# PCM5102a.net
KiCad netlist of a schematic drawn in EAGLE
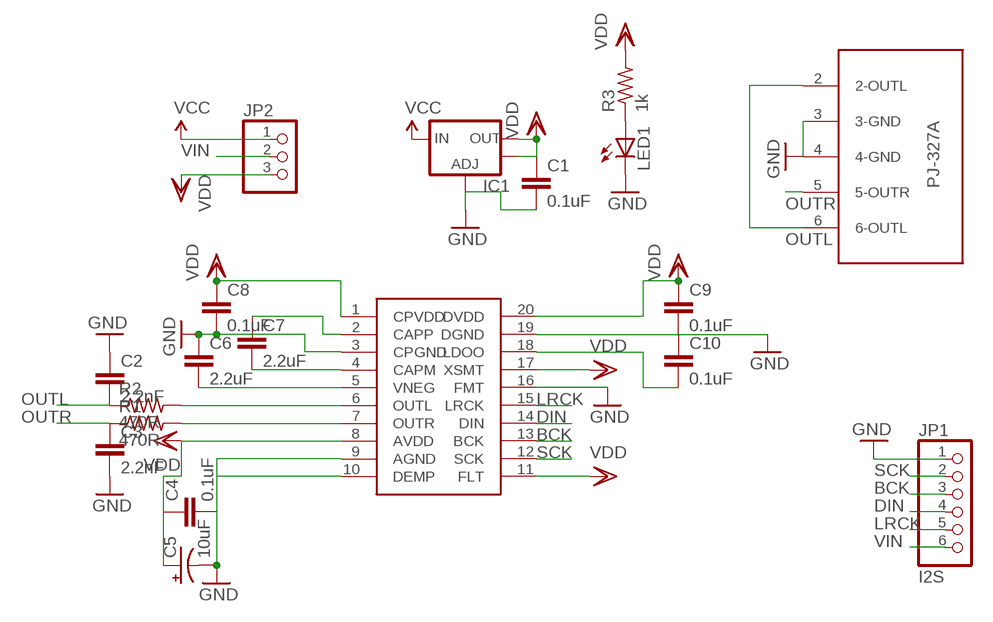
[diagram p0: schematic, sheet 1]

(export (version "E")
  (design (tool "Eeschema 10.0.6"))
  (components
    (comp (ref "C1")
      (value "0.1uF")
      (footprint "eagle-import:1206")
      (libsource (lib "eagle-import") (part "2.2UF-CERCAP-10009"))
    )
    (comp (ref "C2")
      (value "2.2nF")
      (footprint "eagle-import:C5B2.5")
      (libsource (lib "eagle-import") (part "C5/2.5"))
    )
    (comp (ref "C3")
      (value "2.2nF")
      (footprint "eagle-import:C5B2.5")
      (libsource (lib "eagle-import") (part "C5/2.5"))
    )
    (comp (ref "C4")
      (value "0.1uF")
      (footprint "eagle-import:1206")
      (libsource (lib "eagle-import") (part "2.2UF-CERCAP-10009"))
    )
    (comp (ref "C5")
      (value "10uF")
      (footprint "eagle-import:NIPPON_F80")
      (libsource (lib "eagle-import") (part "CAP_POLF80"))
    )
    (comp (ref "C6")
      (value "2.2uF")
      (footprint "eagle-import:1206")
      (libsource (lib "eagle-import") (part "2.2UF-CERCAP-10009"))
    )
    (comp (ref "C7")
      (value "2.2uF")
      (footprint "eagle-import:1206")
      (libsource (lib "eagle-import") (part "2.2UF-CERCAP-10009"))
    )
    (comp (ref "C8")
      (value "0.1uF")
      (footprint "eagle-import:1206")
      (libsource (lib "eagle-import") (part "2.2UF-CERCAP-10009"))
    )
    (comp (ref "C9")
      (value "0.1uF")
      (footprint "eagle-import:1206")
      (libsource (lib "eagle-import") (part "2.2UF-CERCAP-10009"))
    )
    (comp (ref "C10")
      (value "0.1uF")
      (footprint "eagle-import:1206")
      (libsource (lib "eagle-import") (part "2.2UF-CERCAP-10009"))
    )
    (comp (ref "IC1")
      (value "V_REG_LM1117SOT223")
      (footprint "eagle-import:SOT223")
      (libsource (lib "eagle-import") (part "V_REG_LM1117SOT223"))
    )
    (comp (ref "JP1")
      (value "I2S")
      (footprint "eagle-import:1X06_90")
      (libsource (lib "eagle-import") (part "PINHD-1X6/90"))
    )
    (comp (ref "JP2")
      (value "PINHD-1X3")
      (footprint "eagle-import:1X03")
      (libsource (lib "eagle-import") (part "PINHD-1X3"))
    )
    (comp (ref "LED1")
      (value "LEDCHIP-LED0805")
      (footprint "eagle-import:CHIP-LED0805")
      (libsource (lib "eagle-import") (part "LEDCHIP-LED0805"))
    )
    (comp (ref "R1")
      (value "470R")
      (footprint "eagle-import:0207_10")
      (libsource (lib "eagle-import") (part "R-US_0207/10"))
    )
    (comp (ref "R2")
      (value "470R")
      (footprint "eagle-import:0207_10")
      (libsource (lib "eagle-import") (part "R-US_0207/10"))
    )
    (comp (ref "R3")
      (value "1k")
      (footprint "eagle-import:0207_10")
      (libsource (lib "eagle-import") (part "R-US_0207/10"))
    )
    (comp (ref "U$1")
      (value "PCM5102")
      (footprint "eagle-import:TSSOP20")
      (libsource (lib "eagle-import") (part "PCM5102"))
    )
    (comp (ref "U$2")
      (value "PJ-327A")
      (footprint "eagle-import:PJ-327A")
      (libsource (lib "eagle-import") (part "PJ-327A"))
    )
  )
  (nets
    (net (code "1") (name "/BCK") (class "Default")
      (node (ref "JP1") (pin "3") (pinfunction "3_3") (pintype "passive"))
      (node (ref "U$1") (pin "13") (pinfunction "BCK_13") (pintype "bidirectional"))
    )
    (net (code "2") (name "/DIN") (class "Default")
      (node (ref "JP1") (pin "4") (pinfunction "4_4") (pintype "passive"))
      (node (ref "U$1") (pin "14") (pinfunction "DIN_14") (pintype "bidirectional"))
    )
    (net (code "3") (name "/LRCK") (class "Default")
      (node (ref "JP1") (pin "5") (pinfunction "5_5") (pintype "passive"))
      (node (ref "U$1") (pin "15") (pinfunction "LRCK_15") (pintype "bidirectional"))
    )
    (net (code "4") (name "/OUTL") (class "Default")
      (node (ref "C2") (pin "2") (pinfunction "2_2") (pintype "passive"))
      (node (ref "R2") (pin "1") (pinfunction "1_1") (pintype "passive"))
      (node (ref "U$2") (pin "2") (pinfunction "2-OUTL_2") (pintype "bidirectional"))
      (node (ref "U$2") (pin "6") (pinfunction "6-OUTL_6") (pintype "bidirectional"))
    )
    (net (code "5") (name "/OUTR") (class "Default")
      (node (ref "C3") (pin "1") (pinfunction "1_1") (pintype "passive"))
      (node (ref "R1") (pin "1") (pinfunction "1_1") (pintype "passive"))
      (node (ref "U$2") (pin "5") (pinfunction "5-OUTR_5") (pintype "bidirectional"))
    )
    (net (code "6") (name "/SCK") (class "Default")
      (node (ref "JP1") (pin "2") (pinfunction "2_2") (pintype "passive"))
      (node (ref "U$1") (pin "12") (pinfunction "SCK_12") (pintype "bidirectional"))
    )
    (net (code "7") (name "/VIN") (class "Default")
      (node (ref "JP1") (pin "6") (pinfunction "6_6") (pintype "passive"))
      (node (ref "JP2") (pin "2") (pinfunction "2_2") (pintype "passive"))
    )
    (net (code "8") (name "GND") (class "Default")
      (node (ref "C1") (pin "2") (pinfunction "2_2") (pintype "passive"))
      (node (ref "C10") (pin "1") (pinfunction "1_1") (pintype "passive"))
      (node (ref "C2") (pin "1") (pinfunction "1_1") (pintype "passive"))
      (node (ref "C3") (pin "2") (pinfunction "2_2") (pintype "passive"))
      (node (ref "C4") (pin "2") (pinfunction "2_2") (pintype "passive"))
      (node (ref "C5") (pin "-") (pinfunction "-_-") (pintype "passive"))
      (node (ref "C6") (pin "1") (pinfunction "1_1") (pintype "passive"))
      (node (ref "C8") (pin "2") (pinfunction "2_2") (pintype "passive"))
      (node (ref "C9") (pin "2") (pinfunction "2_2") (pintype "passive"))
      (node (ref "IC1") (pin "1") (pinfunction "ADJ_1") (pintype "input"))
      (node (ref "JP1") (pin "1") (pinfunction "1_1") (pintype "passive"))
      (node (ref "LED1") (pin "C") (pinfunction "C_C") (pintype "passive"))
      (node (ref "U$1") (pin "10") (pinfunction "DEMP_10") (pintype "bidirectional"))
      (node (ref "U$1") (pin "16") (pinfunction "FMT_16") (pintype "bidirectional"))
      (node (ref "U$1") (pin "19") (pinfunction "DGND_19") (pintype "bidirectional"))
      (node (ref "U$1") (pin "3") (pinfunction "CPGND_3") (pintype "bidirectional"))
      (node (ref "U$1") (pin "9") (pinfunction "AGND_9") (pintype "bidirectional"))
      (node (ref "U$2") (pin "3") (pinfunction "3-GND_3") (pintype "bidirectional"))
      (node (ref "U$2") (pin "4") (pinfunction "4-GND_4") (pintype "bidirectional"))
    )
    (net (code "9") (name "Net-(LED1-PadA)") (class "Default")
      (node (ref "LED1") (pin "A") (pinfunction "A_A") (pintype "passive"))
      (node (ref "R3") (pin "1") (pinfunction "1_1") (pintype "passive"))
    )
    (net (code "10") (name "Net-(U$1-CAPM)") (class "Default")
      (node (ref "C7") (pin "2") (pinfunction "2_2") (pintype "passive"))
      (node (ref "U$1") (pin "4") (pinfunction "CAPM_4") (pintype "bidirectional"))
    )
    (net (code "11") (name "Net-(U$1-CAPP)") (class "Default")
      (node (ref "C7") (pin "1") (pinfunction "1_1") (pintype "passive"))
      (node (ref "U$1") (pin "2") (pinfunction "CAPP_2") (pintype "bidirectional"))
    )
    (net (code "12") (name "Net-(U$1-LDOO)") (class "Default")
      (node (ref "C10") (pin "2") (pinfunction "2_2") (pintype "passive"))
      (node (ref "U$1") (pin "18") (pinfunction "LDOO_18") (pintype "bidirectional"))
    )
    (net (code "13") (name "Net-(U$1-OUTL)") (class "Default")
      (node (ref "R2") (pin "2") (pinfunction "2_2") (pintype "passive"))
      (node (ref "U$1") (pin "6") (pinfunction "OUTL_6") (pintype "bidirectional"))
    )
    (net (code "14") (name "Net-(U$1-OUTR)") (class "Default")
      (node (ref "R1") (pin "2") (pinfunction "2_2") (pintype "passive"))
      (node (ref "U$1") (pin "7") (pinfunction "OUTR_7") (pintype "bidirectional"))
    )
    (net (code "15") (name "Net-(U$1-VNEG)") (class "Default")
      (node (ref "C6") (pin "2") (pinfunction "2_2") (pintype "passive"))
      (node (ref "U$1") (pin "5") (pinfunction "VNEG_5") (pintype "bidirectional"))
    )
    (net (code "16") (name "VCC") (class "Default")
      (node (ref "IC1") (pin "3") (pinfunction "IN_3") (pintype "input"))
      (node (ref "JP2") (pin "1") (pinfunction "1_1") (pintype "passive"))
    )
    (net (code "17") (name "VDD") (class "Default")
      (node (ref "C1") (pin "1") (pinfunction "1_1") (pintype "passive"))
      (node (ref "C4") (pin "1") (pinfunction "1_1") (pintype "passive"))
      (node (ref "C5") (pin "+") (pinfunction "+_+") (pintype "passive"))
      (node (ref "C8") (pin "1") (pinfunction "1_1") (pintype "passive"))
      (node (ref "C9") (pin "1") (pinfunction "1_1") (pintype "passive"))
      (node (ref "IC1") (pin "2") (pinfunction "OUT_2") (pintype "output"))
      (node (ref "IC1") (pin "4") (pinfunction "OUT_4") (pintype "output"))
      (node (ref "JP2") (pin "3") (pinfunction "3_3") (pintype "passive"))
      (node (ref "R3") (pin "2") (pinfunction "2_2") (pintype "passive"))
      (node (ref "U$1") (pin "1") (pinfunction "CPVDD_1") (pintype "bidirectional"))
      (node (ref "U$1") (pin "11") (pinfunction "FLT_11") (pintype "bidirectional"))
      (node (ref "U$1") (pin "17") (pinfunction "XSMT_17") (pintype "bidirectional"))
      (node (ref "U$1") (pin "20") (pinfunction "DVDD_20") (pintype "bidirectional"))
      (node (ref "U$1") (pin "8") (pinfunction "AVDD_8") (pintype "bidirectional"))
    )
  )
)
